# Meshtastic-DIY_v2_3_TTGO-T18-V30.net
KiCad netlist of a schematic drawn in EAGLE
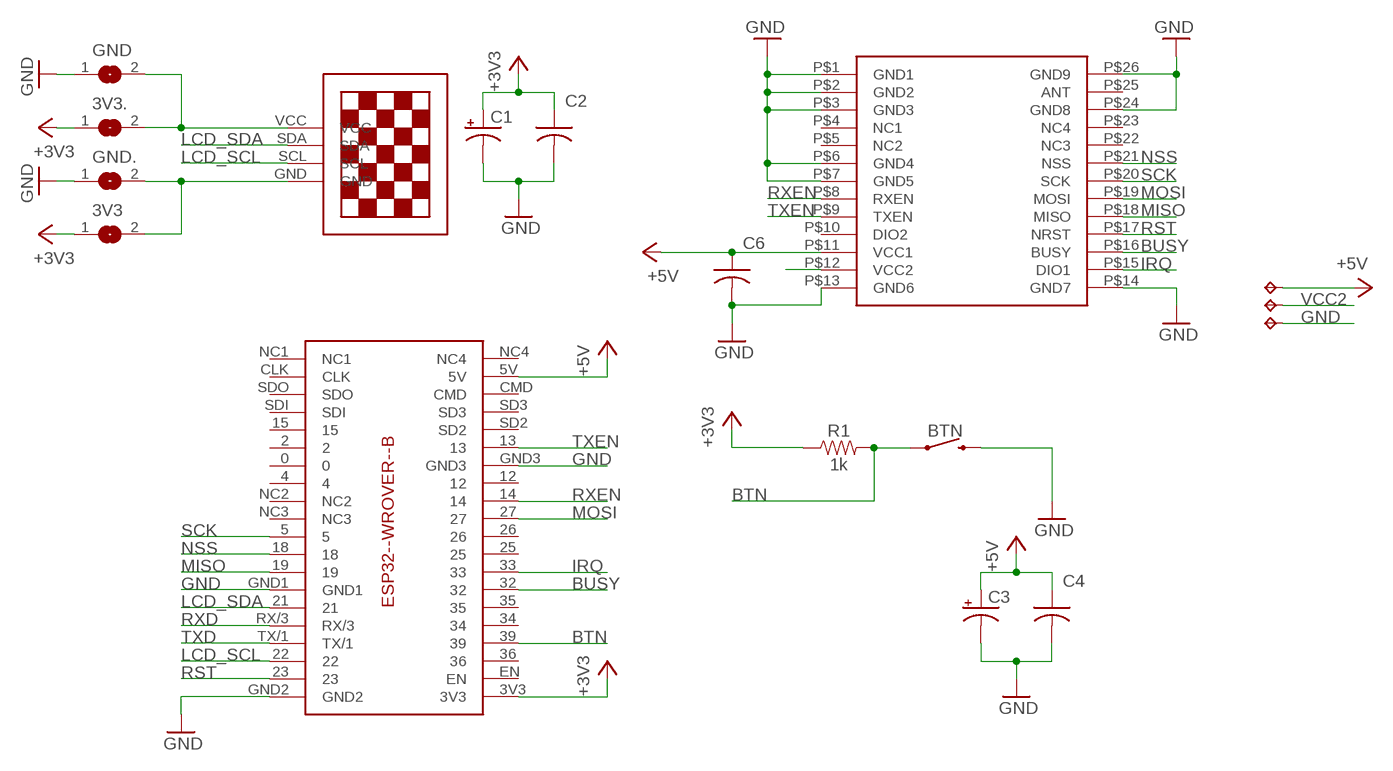
[diagram p0: schematic, sheet 1]

(export (version "E")
  (design (tool "Eeschema 10.0.6"))
  (components
    (comp (ref "3V3") (value "SJ") (footprint "eagle-import:SJ") (libsource (lib "eagle-import") (part "SJ")))
    (comp (ref "3V3.")
      (value "SJ")
      (footprint "eagle-import:SJ")
      (libsource (lib "eagle-import") (part "SJ"))
    )
    (comp (ref "BTN")
      (value "MOMENTARY-SWITCH-SPST-SMD-5.2MM")
      (footprint "eagle-import:TACTILE_SWITCH_SMD_5.2MM")
      (libsource (lib "eagle-import") (part "MOMENTARY-SWITCH-SPST-SMD-5.2MM"))
    )
    (comp (ref "C1")
      (value "100uF")
      (footprint "eagle-import:EIA7343")
      (libsource (lib "eagle-import") (part "100UF-POLAR-EIA7343-10V-10%(TANT)"))
    )
    (comp (ref "C2")
      (value "100nF")
      (footprint "eagle-import:C025-024X044")
      (libsource (lib "eagle-import") (part "C-US025-024X044"))
    )
    (comp (ref "C3")
      (value "100uF")
      (footprint "eagle-import:EIA7343")
      (libsource (lib "eagle-import") (part "100UF-POLAR-EIA7343-10V-10%(TANT)"))
    )
    (comp (ref "C4")
      (value "100nF")
      (footprint "eagle-import:C025-024X044")
      (libsource (lib "eagle-import") (part "C-US025-024X044"))
    )
    (comp (ref "C6")
      (value "100nF")
      (footprint "eagle-import:C025-024X044")
      (libsource (lib "eagle-import") (part "C-US025-024X044"))
    )
    (comp (ref "GND") (value "SJ") (footprint "eagle-import:SJ") (libsource (lib "eagle-import") (part "SJ")))
    (comp (ref "GND.")
      (value "SJ")
      (footprint "eagle-import:SJ")
      (libsource (lib "eagle-import") (part "SJ"))
    )
    (comp (ref "R1")
      (value "1k")
      (footprint "eagle-import:AXIAL-0.1")
      (libsource (lib "eagle-import") (part "1KOHM-VERT-1/4W-1%"))
    )
    (comp (ref "TP1")
      (value "TPTP14SQ")
      (footprint "eagle-import:TP14SQ")
      (libsource (lib "eagle-import") (part "TPTP14SQ"))
    )
    (comp (ref "TP2")
      (value "TPTP14SQ")
      (footprint "eagle-import:TP14SQ")
      (libsource (lib "eagle-import") (part "TPTP14SQ"))
    )
    (comp (ref "TP3")
      (value "TPTP14SQ")
      (footprint "eagle-import:TP14SQ")
      (libsource (lib "eagle-import") (part "TPTP14SQ"))
    )
    (comp (ref "U$1")
      (value "13\"OLED13\"OLED")
      (footprint "eagle-import:1.3_OLED")
      (libsource (lib "eagle-import") (part "13{dblquote}OLED13{dblquote}OLED"))
    )
    (comp (ref "U$2")
      (value "E22-XXXMXXS")
      (footprint "eagle-import:E22-XXXMXXS")
      (libsource (lib "eagle-import") (part "E22-XXXMXXS"))
    )
    (comp (ref "U$4")
      (value "TTGO-T18_V3")
      (footprint "eagle-import:TTGO-T18_V3")
      (libsource (lib "eagle-import") (part "TTGO-T18_V3"))
    )
  )
  (nets
    (net (code "1") (name "+3V3") (class "Default")
      (node (ref "3V3") (pin "1") (pinfunction "1_1") (pintype "passive"))
      (node (ref "3V3.") (pin "1") (pinfunction "1_1") (pintype "passive"))
      (node (ref "C1") (pin "A") (pinfunction "+_A") (pintype "passive"))
      (node (ref "C2") (pin "1") (pinfunction "1_1") (pintype "passive"))
      (node (ref "R1") (pin "P$1") (pinfunction "1_P$1") (pintype "passive"))
      (node (ref "U$4") (pin "3V3") (pinfunction "3V3_3V3") (pintype "bidirectional"))
    )
    (net (code "2") (name "+5V") (class "Default")
      (node (ref "C3") (pin "A") (pinfunction "+_A") (pintype "passive"))
      (node (ref "C4") (pin "1") (pinfunction "1_1") (pintype "passive"))
      (node (ref "C6") (pin "1") (pinfunction "1_1") (pintype "passive"))
      (node (ref "TP1") (pin "TP") (pinfunction "TP_TP") (pintype "input"))
      (node (ref "U$2") (pin "P$11") (pinfunction "VCC1_P$11") (pintype "bidirectional"))
      (node (ref "U$4") (pin "5V") (pinfunction "5V_5V") (pintype "bidirectional"))
    )
    (net (code "3") (name "/BTN") (class "Default")
      (node (ref "BTN") (pin "1") (pinfunction "1_1") (pintype "passive"))
      (node (ref "R1") (pin "P$2") (pinfunction "2_P$2") (pintype "passive"))
      (node (ref "U$4") (pin "39") (pinfunction "39_39") (pintype "bidirectional"))
    )
    (net (code "4") (name "/BUSY") (class "Default")
      (node (ref "U$2") (pin "P$16") (pinfunction "BUSY_P$16") (pintype "bidirectional"))
      (node (ref "U$4") (pin "32") (pinfunction "32_32") (pintype "bidirectional"))
    )
    (net (code "5") (name "/IRQ") (class "Default")
      (node (ref "U$2") (pin "P$15") (pinfunction "DIO1_P$15") (pintype "bidirectional"))
      (node (ref "U$4") (pin "33") (pinfunction "33_33") (pintype "bidirectional"))
    )
    (net (code "6") (name "/LCD_SCL") (class "Default")
      (node (ref "U$1") (pin "SCL") (pinfunction "SCL_SCL") (pintype "bidirectional"))
      (node (ref "U$4") (pin "22") (pinfunction "22_22") (pintype "bidirectional"))
    )
    (net (code "7") (name "/LCD_SDA") (class "Default")
      (node (ref "U$1") (pin "SDA") (pinfunction "SDA_SDA") (pintype "bidirectional"))
      (node (ref "U$4") (pin "21") (pinfunction "21_21") (pintype "bidirectional"))
    )
    (net (code "8") (name "/MISO") (class "Default")
      (node (ref "U$2") (pin "P$18") (pinfunction "MISO_P$18") (pintype "bidirectional"))
      (node (ref "U$4") (pin "19") (pinfunction "19_19") (pintype "bidirectional"))
    )
    (net (code "9") (name "/MOSI") (class "Default")
      (node (ref "U$2") (pin "P$19") (pinfunction "MOSI_P$19") (pintype "bidirectional"))
      (node (ref "U$4") (pin "27") (pinfunction "27_27") (pintype "bidirectional"))
    )
    (net (code "10") (name "/NSS") (class "Default")
      (node (ref "U$2") (pin "P$21") (pinfunction "NSS_P$21") (pintype "bidirectional"))
      (node (ref "U$4") (pin "18") (pinfunction "18_18") (pintype "bidirectional"))
    )
    (net (code "11") (name "/RST") (class "Default")
      (node (ref "U$2") (pin "P$17") (pinfunction "NRST_P$17") (pintype "bidirectional"))
      (node (ref "U$4") (pin "23") (pinfunction "23_23") (pintype "bidirectional"))
    )
    (net (code "12") (name "/RXD") (class "Default")
      (node (ref "U$4") (pin "RX/3") (pinfunction "RX/3_RX/3") (pintype "bidirectional"))
    )
    (net (code "13") (name "/RXEN") (class "Default")
      (node (ref "U$2") (pin "P$8") (pinfunction "RXEN_P$8") (pintype "bidirectional"))
      (node (ref "U$4") (pin "14") (pinfunction "14_14") (pintype "bidirectional"))
    )
    (net (code "14") (name "/SCK") (class "Default")
      (node (ref "U$2") (pin "P$20") (pinfunction "SCK_P$20") (pintype "bidirectional"))
      (node (ref "U$4") (pin "5") (pinfunction "5_5") (pintype "bidirectional"))
    )
    (net (code "15") (name "/TXD") (class "Default")
      (node (ref "U$4") (pin "TX/1") (pinfunction "TX/1_TX/1") (pintype "bidirectional"))
    )
    (net (code "16") (name "/TXEN") (class "Default")
      (node (ref "U$2") (pin "P$9") (pinfunction "TXEN_P$9") (pintype "bidirectional"))
      (node (ref "U$4") (pin "13") (pinfunction "13_13") (pintype "bidirectional"))
    )
    (net (code "17") (name "/VCC2") (class "Default")
      (node (ref "TP2") (pin "TP") (pinfunction "TP_TP") (pintype "input"))
      (node (ref "U$2") (pin "P$12") (pinfunction "VCC2_P$12") (pintype "bidirectional"))
    )
    (net (code "18") (name "GND") (class "Default")
      (node (ref "BTN") (pin "3") (pinfunction "2_3") (pintype "passive"))
      (node (ref "C1") (pin "C") (pinfunction "-_C") (pintype "passive"))
      (node (ref "C2") (pin "2") (pinfunction "2_2") (pintype "passive"))
      (node (ref "C3") (pin "C") (pinfunction "-_C") (pintype "passive"))
      (node (ref "C4") (pin "2") (pinfunction "2_2") (pintype "passive"))
      (node (ref "C6") (pin "2") (pinfunction "2_2") (pintype "passive"))
      (node (ref "GND") (pin "1") (pinfunction "1_1") (pintype "passive"))
      (node (ref "GND.") (pin "1") (pinfunction "1_1") (pintype "passive"))
      (node (ref "TP3") (pin "TP") (pinfunction "TP_TP") (pintype "input"))
      (node (ref "U$2") (pin "P$1") (pinfunction "GND1_P$1") (pintype "bidirectional"))
      (node (ref "U$2") (pin "P$13") (pinfunction "GND6_P$13") (pintype "bidirectional"))
      (node (ref "U$2") (pin "P$14") (pinfunction "GND7_P$14") (pintype "bidirectional"))
      (node (ref "U$2") (pin "P$2") (pinfunction "GND2_P$2") (pintype "bidirectional"))
      (node (ref "U$2") (pin "P$24") (pinfunction "GND8_P$24") (pintype "bidirectional"))
      (node (ref "U$2") (pin "P$26") (pinfunction "GND9_P$26") (pintype "bidirectional"))
      (node (ref "U$2") (pin "P$3") (pinfunction "GND3_P$3") (pintype "bidirectional"))
      (node (ref "U$2") (pin "P$6") (pinfunction "GND4_P$6") (pintype "bidirectional"))
      (node (ref "U$2") (pin "P$7") (pinfunction "GND5_P$7") (pintype "bidirectional"))
      (node (ref "U$4") (pin "GND1") (pinfunction "GND1_GND1") (pintype "bidirectional"))
      (node (ref "U$4") (pin "GND2") (pinfunction "GND2_GND2") (pintype "bidirectional"))
      (node (ref "U$4") (pin "GND3") (pinfunction "GND3_GND3") (pintype "bidirectional"))
    )
    (net (code "19") (name "Net-(3V3-Pad2)") (class "Default")
      (node (ref "3V3") (pin "2") (pinfunction "2_2") (pintype "passive"))
      (node (ref "GND.") (pin "2") (pinfunction "2_2") (pintype "passive"))
      (node (ref "U$1") (pin "GND") (pinfunction "GND_GND") (pintype "bidirectional"))
    )
    (net (code "20") (name "Net-(3V3.-Pad2)") (class "Default")
      (node (ref "3V3.") (pin "2") (pinfunction "2_2") (pintype "passive"))
      (node (ref "GND") (pin "2") (pinfunction "2_2") (pintype "passive"))
      (node (ref "U$1") (pin "VCC") (pinfunction "VCC_VCC") (pintype "bidirectional"))
    )
    (net (code "21") (name "unconnected-(U$2-ANT-PadP$25)") (class "Default")
      (node (ref "U$2") (pin "P$25") (pinfunction "ANT_P$25") (pintype "bidirectional"))
    )
    (net (code "22") (name "unconnected-(U$2-DIO2-PadP$10)") (class "Default")
      (node (ref "U$2") (pin "P$10") (pinfunction "DIO2_P$10") (pintype "bidirectional"))
    )
    (net (code "23") (name "unconnected-(U$2-NC1-PadP$4)") (class "Default")
      (node (ref "U$2") (pin "P$4") (pinfunction "NC1_P$4") (pintype "bidirectional"))
    )
    (net (code "24") (name "unconnected-(U$2-NC2-PadP$5)") (class "Default")
      (node (ref "U$2") (pin "P$5") (pinfunction "NC2_P$5") (pintype "bidirectional"))
    )
    (net (code "25") (name "unconnected-(U$2-NC3-PadP$22)") (class "Default")
      (node (ref "U$2") (pin "P$22") (pinfunction "NC3_P$22") (pintype "bidirectional"))
    )
    (net (code "26") (name "unconnected-(U$2-NC4-PadP$23)") (class "Default")
      (node (ref "U$2") (pin "P$23") (pinfunction "NC4_P$23") (pintype "bidirectional"))
    )
    (net (code "27") (name "unconnected-(U$4-Pad0)") (class "Default")
      (node (ref "U$4") (pin "0") (pinfunction "0_0") (pintype "bidirectional"))
    )
    (net (code "28") (name "unconnected-(U$4-Pad2)") (class "Default")
      (node (ref "U$4") (pin "2") (pinfunction "2_2") (pintype "bidirectional"))
    )
    (net (code "29") (name "unconnected-(U$4-Pad4)") (class "Default")
      (node (ref "U$4") (pin "4") (pinfunction "4_4") (pintype "bidirectional"))
    )
    (net (code "30") (name "unconnected-(U$4-Pad12)") (class "Default")
      (node (ref "U$4") (pin "12") (pinfunction "12_12") (pintype "bidirectional"))
    )
    (net (code "31") (name "unconnected-(U$4-Pad15)") (class "Default")
      (node (ref "U$4") (pin "15") (pinfunction "15_15") (pintype "bidirectional"))
    )
    (net (code "32") (name "unconnected-(U$4-Pad25)") (class "Default")
      (node (ref "U$4") (pin "25") (pinfunction "25_25") (pintype "bidirectional"))
    )
    (net (code "33") (name "unconnected-(U$4-Pad26)") (class "Default")
      (node (ref "U$4") (pin "26") (pinfunction "26_26") (pintype "bidirectional"))
    )
    (net (code "34") (name "unconnected-(U$4-Pad34)") (class "Default")
      (node (ref "U$4") (pin "34") (pinfunction "34_34") (pintype "bidirectional"))
    )
    (net (code "35") (name "unconnected-(U$4-Pad35)") (class "Default")
      (node (ref "U$4") (pin "35") (pinfunction "35_35") (pintype "bidirectional"))
    )
    (net (code "36") (name "unconnected-(U$4-Pad36)") (class "Default")
      (node (ref "U$4") (pin "36") (pinfunction "36_36") (pintype "bidirectional"))
    )
    (net (code "37") (name "unconnected-(U$4-PadCLK)") (class "Default")
      (node (ref "U$4") (pin "CLK") (pinfunction "CLK_CLK") (pintype "bidirectional"))
    )
    (net (code "38") (name "unconnected-(U$4-PadCMD)") (class "Default")
      (node (ref "U$4") (pin "CMD") (pinfunction "CMD_CMD") (pintype "bidirectional"))
    )
    (net (code "39") (name "unconnected-(U$4-PadEN)") (class "Default")
      (node (ref "U$4") (pin "EN") (pinfunction "EN_EN") (pintype "bidirectional"))
    )
    (net (code "40") (name "unconnected-(U$4-PadNC1)") (class "Default")
      (node (ref "U$4") (pin "NC1") (pinfunction "NC1_NC1") (pintype "bidirectional"))
    )
    (net (code "41") (name "unconnected-(U$4-PadNC2)") (class "Default")
      (node (ref "U$4") (pin "NC2") (pinfunction "NC2_NC2") (pintype "bidirectional"))
    )
    (net (code "42") (name "unconnected-(U$4-PadNC3)") (class "Default")
      (node (ref "U$4") (pin "NC3") (pinfunction "NC3_NC3") (pintype "bidirectional"))
    )
    (net (code "43") (name "unconnected-(U$4-PadNC4)") (class "Default")
      (node (ref "U$4") (pin "NC4") (pinfunction "NC4_NC4") (pintype "bidirectional"))
    )
    (net (code "44") (name "unconnected-(U$4-PadSD2)") (class "Default")
      (node (ref "U$4") (pin "SD2") (pinfunction "SD2_SD2") (pintype "bidirectional"))
    )
    (net (code "45") (name "unconnected-(U$4-PadSD3)") (class "Default")
      (node (ref "U$4") (pin "SD3") (pinfunction "SD3_SD3") (pintype "bidirectional"))
    )
    (net (code "46") (name "unconnected-(U$4-PadSDI)") (class "Default")
      (node (ref "U$4") (pin "SDI") (pinfunction "SDI_SDI") (pintype "bidirectional"))
    )
    (net (code "47") (name "unconnected-(U$4-PadSDO)") (class "Default")
      (node (ref "U$4") (pin "SDO") (pinfunction "SDO_SDO") (pintype "bidirectional"))
    )
  )
)
